# 4pin-bus.net
KiCad netlist of a schematic drawn in EAGLE
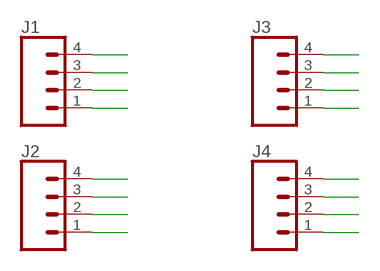
[diagram p0: schematic, sheet 1]

(export (version "E")
  (design (tool "Eeschema 10.0.6"))
  (components
    (comp (ref "J1")
      (value "CONN_04")
      (footprint "eagle-import:1X04")
      (libsource (lib "eagle-import") (part "CONN_04"))
    )
    (comp (ref "J2")
      (value "CONN_04")
      (footprint "eagle-import:1X04")
      (libsource (lib "eagle-import") (part "CONN_04"))
    )
    (comp (ref "J3")
      (value "CONN_04")
      (footprint "eagle-import:1X04")
      (libsource (lib "eagle-import") (part "CONN_04"))
    )
    (comp (ref "J4")
      (value "CONN_04")
      (footprint "eagle-import:1X04")
      (libsource (lib "eagle-import") (part "CONN_04"))
    )
  )
  (nets
    (net (code "1") (name "/A") (class "Default")
      (node (ref "J1") (pin "1") (pinfunction "1_1") (pintype "passive"))
      (node (ref "J2") (pin "1") (pinfunction "1_1") (pintype "passive"))
      (node (ref "J3") (pin "1") (pinfunction "1_1") (pintype "passive"))
      (node (ref "J4") (pin "1") (pinfunction "1_1") (pintype "passive"))
    )
    (net (code "2") (name "/B") (class "Default")
      (node (ref "J1") (pin "2") (pinfunction "2_2") (pintype "passive"))
      (node (ref "J2") (pin "2") (pinfunction "2_2") (pintype "passive"))
      (node (ref "J3") (pin "2") (pinfunction "2_2") (pintype "passive"))
      (node (ref "J4") (pin "2") (pinfunction "2_2") (pintype "passive"))
    )
    (net (code "3") (name "/C") (class "Default")
      (node (ref "J1") (pin "3") (pinfunction "3_3") (pintype "passive"))
      (node (ref "J2") (pin "3") (pinfunction "3_3") (pintype "passive"))
      (node (ref "J3") (pin "3") (pinfunction "3_3") (pintype "passive"))
      (node (ref "J4") (pin "3") (pinfunction "3_3") (pintype "passive"))
    )
    (net (code "4") (name "/D") (class "Default")
      (node (ref "J1") (pin "4") (pinfunction "4_4") (pintype "passive"))
      (node (ref "J2") (pin "4") (pinfunction "4_4") (pintype "passive"))
      (node (ref "J3") (pin "4") (pinfunction "4_4") (pintype "passive"))
      (node (ref "J4") (pin "4") (pinfunction "4_4") (pintype "passive"))
    )
  )
)
